# SCH_proyecto-mme_Antonio-Martinez_2025-0.net
KiCad netlist of a schematic drawn in EasyEDA
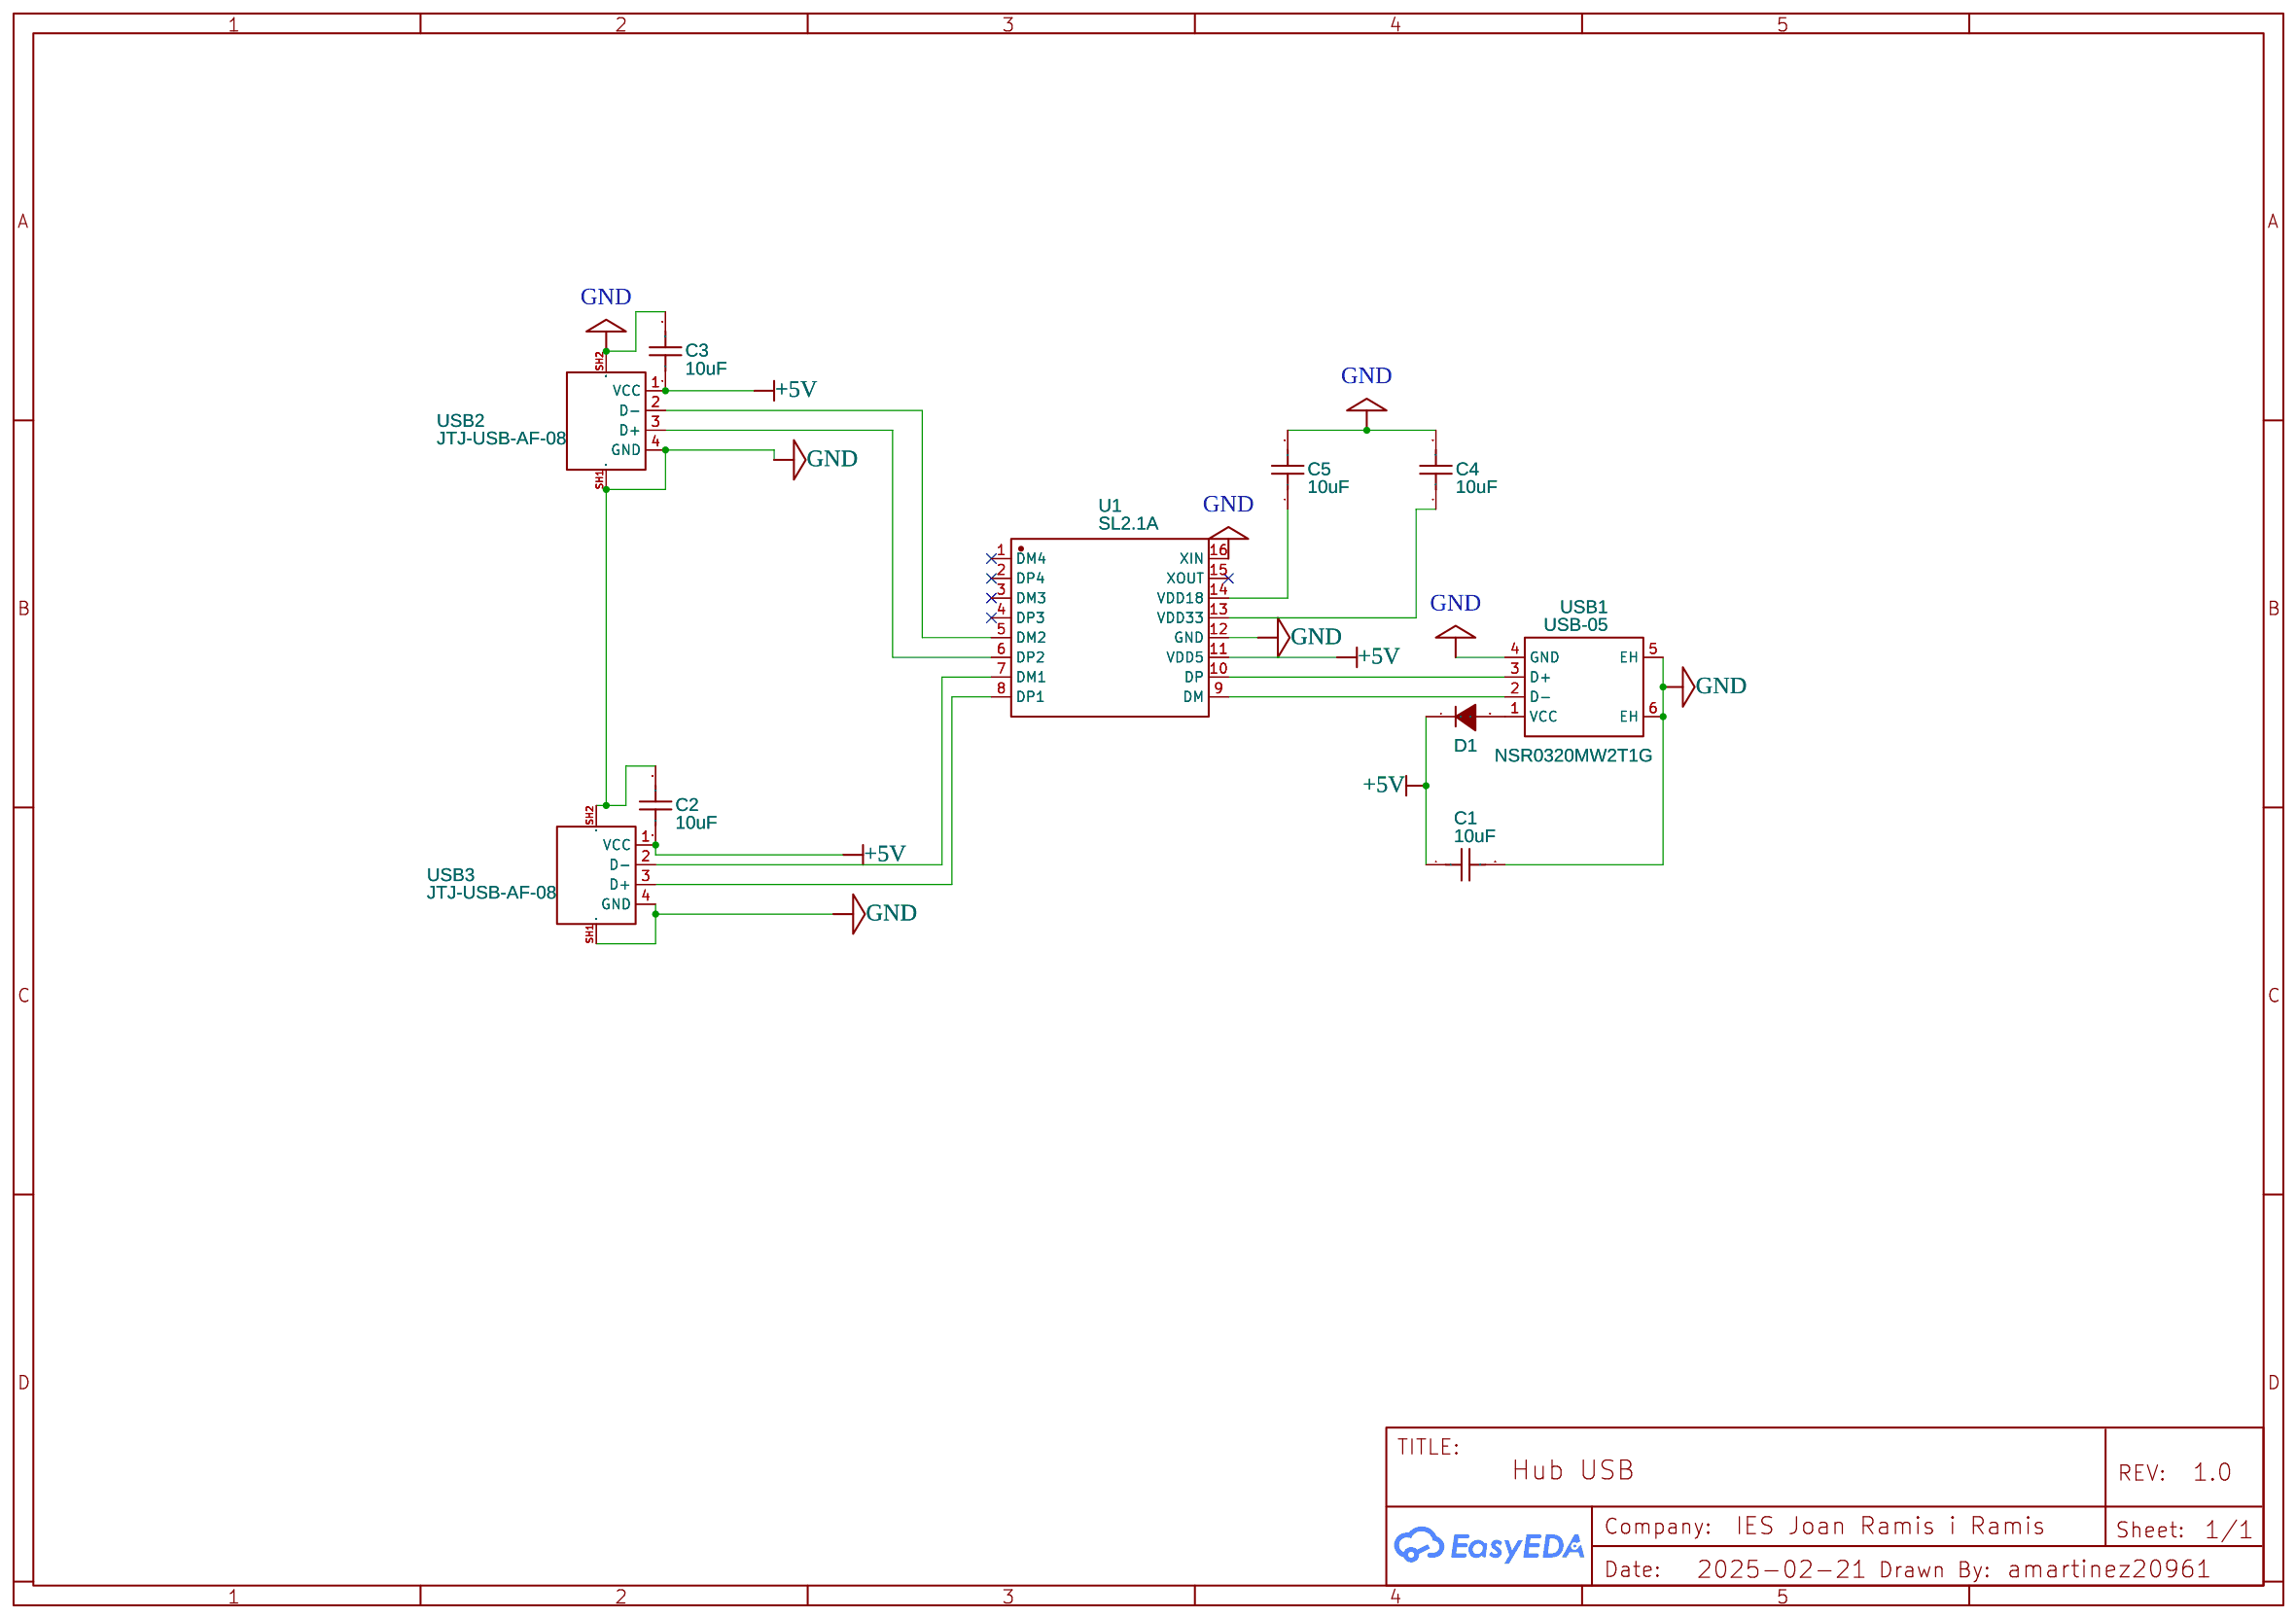
[diagram p0: schematic sheet]

(export (version "E")
  (design (tool "Eeschema 10.0.6"))
  (components
    (comp (ref "C1")
      (value "10uF")
      (fields
        (field (name "Manufacturer Part") "CL10A106KP8NNNC")
        (field (name "Manufacturer") "SAMSUNG(三星)")
      )
      (libsource (lib "") (part "CL10A106KP8NNNC_1"))
    )
    (comp (ref "C2")
      (value "10uF")
      (fields
        (field (name "Manufacturer Part") "CL10A106KP8NNNC")
        (field (name "Manufacturer") "SAMSUNG(三星)")
      )
      (libsource (lib "") (part "CL10A106KP8NNNC"))
    )
    (comp (ref "C3")
      (value "10uF")
      (fields
        (field (name "Manufacturer Part") "CL10A106KP8NNNC")
        (field (name "Manufacturer") "SAMSUNG(三星)")
      )
      (libsource (lib "") (part "CL10A106KP8NNNC"))
    )
    (comp (ref "C4")
      (value "10uF")
      (fields
        (field (name "Manufacturer Part") "CL10A106KP8NNNC")
        (field (name "Manufacturer") "SAMSUNG(三星)")
      )
      (libsource (lib "") (part "CL10A106KP8NNNC"))
    )
    (comp (ref "C5")
      (value "10uF")
      (fields
        (field (name "Manufacturer Part") "CL10A106KP8NNNC")
        (field (name "Manufacturer") "SAMSUNG(三星)")
      )
      (libsource (lib "") (part "CL10A106KP8NNNC"))
    )
    (comp (ref "D1")
      (value "NSR0320MW2T1G")
      (fields (field (name "Manufacturer") "onsemi(安森美)"))
      (libsource (lib "") (part "NSR0320MW2T1G"))
    )
    (comp (ref "U1")
      (value "SL2.1A")
      (fields (field (name "Manufacturer") "CoreChips(和芯润德)"))
      (libsource (lib "") (part "SL2.1A"))
    )
    (comp (ref "USB1")
      (value "USB-05")
      (fields (field (name "Manufacturer") "SOFNG(硕方)"))
      (libsource (lib "") (part "USB-05"))
    )
    (comp (ref "USB2")
      (value "JTJ-USB-AF-08")
      (fields (field (name "Manufacturer Part") "902-131A1011D10100") (field (name "Manufacturer") "精拓金"))
      (libsource (lib "") (part "JTJ-USB-AF-08"))
    )
    (comp (ref "USB3")
      (value "JTJ-USB-AF-08")
      (fields (field (name "Manufacturer Part") "902-131A1011D10100") (field (name "Manufacturer") "精拓金"))
      (libsource (lib "") (part "JTJ-USB-AF-08"))
    )
  )
  (nets
    (net (code "1") (name "+5V") (class "Default")
      (node (ref "C1") (pin "1") (pinfunction "1_1") (pintype "unspecified"))
      (node (ref "C2") (pin "1") (pinfunction "1_1") (pintype "unspecified"))
      (node (ref "C3") (pin "1") (pinfunction "1_1") (pintype "unspecified"))
      (node (ref "D1") (pin "1") (pinfunction "C_1") (pintype "unspecified"))
      (node (ref "U1") (pin "11") (pinfunction "VDD5_11") (pintype "unspecified"))
      (node (ref "USB2") (pin "1") (pinfunction "VCC_1") (pintype "input"))
      (node (ref "USB3") (pin "1") (pinfunction "VCC_1") (pintype "input"))
    )
    (net (code "2") (name "GND") (class "Default")
      (node (ref "C1") (pin "2") (pinfunction "2_2") (pintype "unspecified"))
      (node (ref "C2") (pin "2") (pinfunction "2_2") (pintype "unspecified"))
      (node (ref "C3") (pin "2") (pinfunction "2_2") (pintype "unspecified"))
      (node (ref "C4") (pin "2") (pinfunction "2_2") (pintype "unspecified"))
      (node (ref "C5") (pin "2") (pinfunction "2_2") (pintype "unspecified"))
      (node (ref "U1") (pin "12") (pinfunction "GND_12") (pintype "unspecified"))
      (node (ref "U1") (pin "16") (pinfunction "XIN_16") (pintype "unspecified"))
      (node (ref "USB1") (pin "4") (pinfunction "GND_4") (pintype "input"))
      (node (ref "USB1") (pin "5") (pinfunction "EH_5") (pintype "unspecified"))
      (node (ref "USB1") (pin "6") (pinfunction "EH_6") (pintype "unspecified"))
      (node (ref "USB2") (pin "4") (pinfunction "GND_4") (pintype "input"))
      (node (ref "USB2") (pin "SH1") (pinfunction "SH1_SH1") (pintype "unspecified"))
      (node (ref "USB2") (pin "SH2") (pinfunction "SH2_SH2") (pintype "unspecified"))
      (node (ref "USB3") (pin "4") (pinfunction "GND_4") (pintype "input"))
      (node (ref "USB3") (pin "SH1") (pinfunction "SH1_SH1") (pintype "unspecified"))
      (node (ref "USB3") (pin "SH2") (pinfunction "SH2_SH2") (pintype "unspecified"))
    )
    (net (code "3") (name "Net-(D1-A)") (class "Default")
      (node (ref "D1") (pin "2") (pinfunction "A_2") (pintype "unspecified"))
      (node (ref "USB1") (pin "1") (pinfunction "VCC_1") (pintype "input"))
    )
    (net (code "4") (name "Net-(U1-DM)") (class "Default")
      (node (ref "U1") (pin "9") (pinfunction "DM_9") (pintype "unspecified"))
      (node (ref "USB1") (pin "2") (pinfunction "D-_2") (pintype "input"))
    )
    (net (code "5") (name "Net-(U1-DM1)") (class "Default")
      (node (ref "U1") (pin "7") (pinfunction "DM1_7") (pintype "unspecified"))
      (node (ref "USB3") (pin "2") (pinfunction "D-_2") (pintype "input"))
    )
    (net (code "6") (name "Net-(U1-DM2)") (class "Default")
      (node (ref "U1") (pin "5") (pinfunction "DM2_5") (pintype "unspecified"))
      (node (ref "USB2") (pin "2") (pinfunction "D-_2") (pintype "input"))
    )
    (net (code "7") (name "Net-(U1-DP)") (class "Default")
      (node (ref "U1") (pin "10") (pinfunction "DP_10") (pintype "unspecified"))
      (node (ref "USB1") (pin "3") (pinfunction "D+_3") (pintype "input"))
    )
    (net (code "8") (name "Net-(U1-DP1)") (class "Default")
      (node (ref "U1") (pin "8") (pinfunction "DP1_8") (pintype "unspecified"))
      (node (ref "USB3") (pin "3") (pinfunction "D+_3") (pintype "input"))
    )
    (net (code "9") (name "Net-(U1-DP2)") (class "Default")
      (node (ref "U1") (pin "6") (pinfunction "DP2_6") (pintype "unspecified"))
      (node (ref "USB2") (pin "3") (pinfunction "D+_3") (pintype "input"))
    )
    (net (code "10") (name "Net-(U1-VDD18)") (class "Default")
      (node (ref "C5") (pin "1") (pinfunction "1_1") (pintype "unspecified"))
      (node (ref "U1") (pin "14") (pinfunction "VDD18_14") (pintype "unspecified"))
    )
    (net (code "11") (name "Net-(U1-VDD33)") (class "Default")
      (node (ref "C4") (pin "1") (pinfunction "1_1") (pintype "unspecified"))
      (node (ref "U1") (pin "13") (pinfunction "VDD33_13") (pintype "unspecified"))
    )
    (net (code "12") (name "unconnected-(U1-DM3-Pad3)") (class "Default")
      (node (ref "U1") (pin "3") (pinfunction "DM3_3") (pintype "unspecified+no_connect"))
    )
    (net (code "13") (name "unconnected-(U1-DM4-Pad1)") (class "Default")
      (node (ref "U1") (pin "1") (pinfunction "DM4_1") (pintype "unspecified+no_connect"))
    )
    (net (code "14") (name "unconnected-(U1-DP3-Pad4)") (class "Default")
      (node (ref "U1") (pin "4") (pinfunction "DP3_4") (pintype "unspecified+no_connect"))
    )
    (net (code "15") (name "unconnected-(U1-DP4-Pad2)") (class "Default")
      (node (ref "U1") (pin "2") (pinfunction "DP4_2") (pintype "unspecified+no_connect"))
    )
    (net (code "16") (name "unconnected-(U1-XOUT-Pad15)") (class "Default")
      (node (ref "U1") (pin "15") (pinfunction "XOUT_15") (pintype "unspecified+no_connect"))
    )
  )
)
